# power-switching-TPS6211x.net
KiCad netlist of a schematic drawn in EAGLE
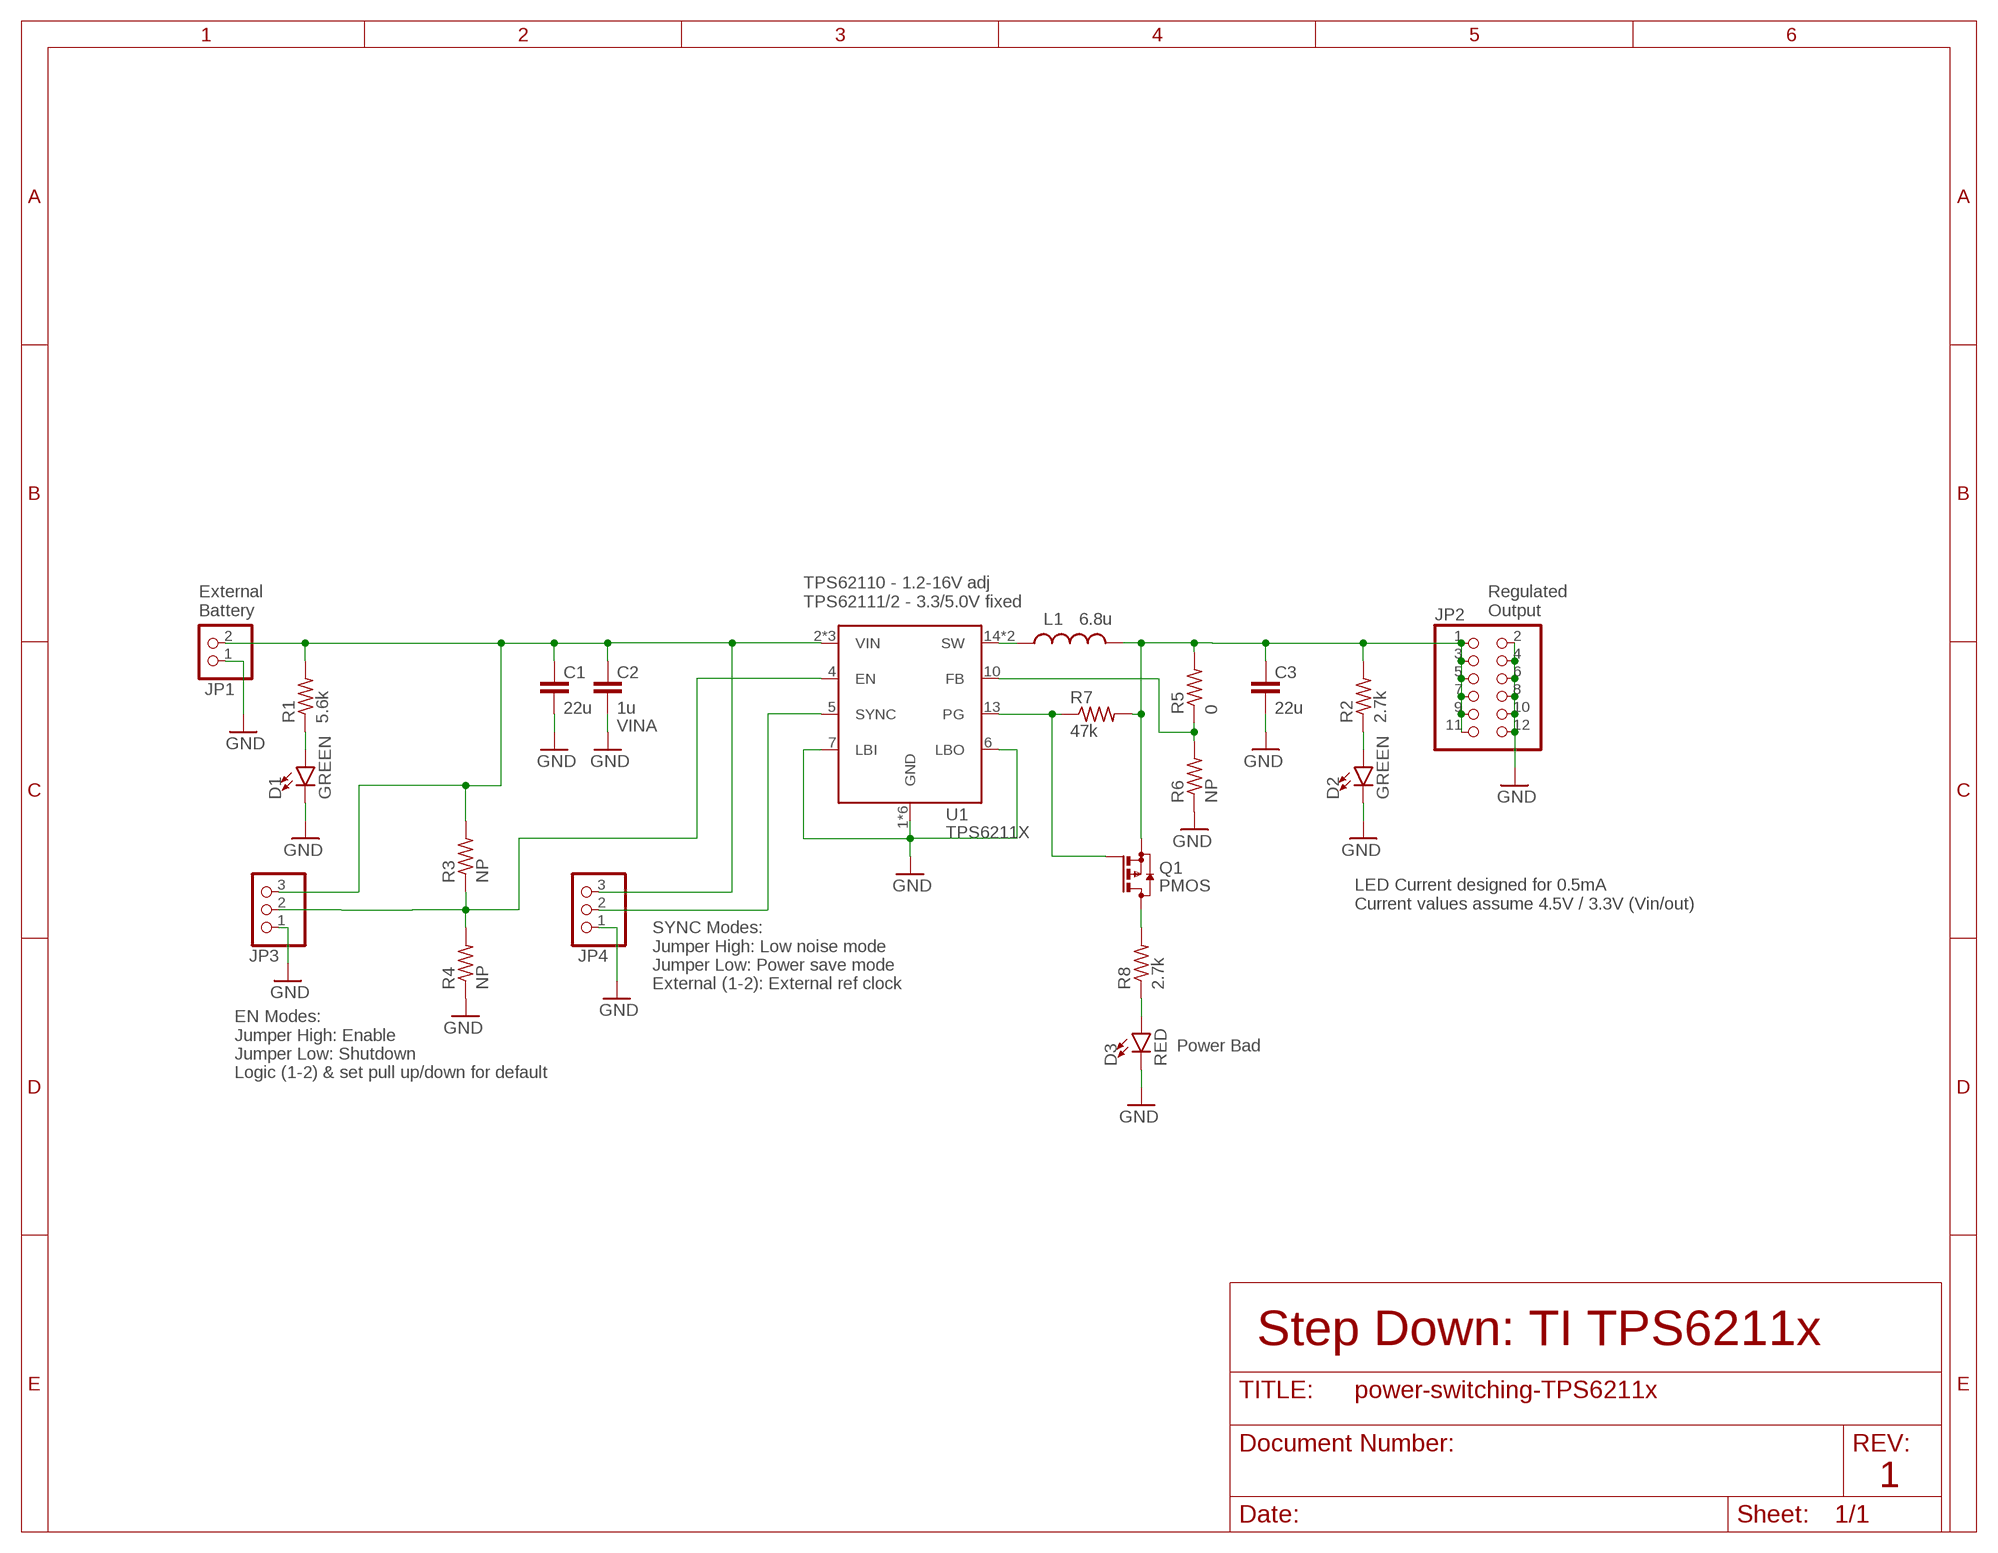
[diagram p0: schematic, sheet 1]

(export (version "E")
  (design (tool "Eeschema 10.0.6"))
  (components
    (comp (ref "C1")
      (value "22u")
      (footprint "eagle-import:1206-B")
      (libsource (lib "eagle-import") (part "C-EU1206-B"))
    )
    (comp (ref "C2")
      (value "1u")
      (footprint "eagle-import:.0603-B-NOSILK")
      (libsource (lib "eagle-import") (part "C-EU0603-B-NOSILK"))
    )
    (comp (ref "C3")
      (value "22u")
      (footprint "eagle-import:1206-B")
      (libsource (lib "eagle-import") (part "C-EU1206-B"))
    )
    (comp (ref "D1")
      (value "GREEN")
      (footprint "eagle-import:LED-0603")
      (libsource (lib "eagle-import") (part "LED-GREEN0603"))
    )
    (comp (ref "D2")
      (value "GREEN")
      (footprint "eagle-import:LED-0603")
      (libsource (lib "eagle-import") (part "LED-GREEN0603"))
    )
    (comp (ref "D3")
      (value "RED")
      (footprint "eagle-import:LED-0603")
      (libsource (lib "eagle-import") (part "LED-GREEN0603"))
    )
    (comp (ref "JP1")
      (value "PINHD-1X2")
      (footprint "eagle-import:1X02")
      (libsource (lib "eagle-import") (part "PINHD-1X2"))
    )
    (comp (ref "JP2")
      (value "PINHD-2X6")
      (footprint "eagle-import:2X06")
      (libsource (lib "eagle-import") (part "PINHD-2X6"))
    )
    (comp (ref "JP3")
      (value "PINHD-1X3")
      (footprint "eagle-import:1X03")
      (libsource (lib "eagle-import") (part "PINHD-1X3"))
    )
    (comp (ref "JP4")
      (value "PINHD-1X3")
      (footprint "eagle-import:1X03")
      (libsource (lib "eagle-import") (part "PINHD-1X3"))
    )
    (comp (ref "L1")
      (value "6.8u")
      (footprint "eagle-import:ECS-MPI4040")
      (fields (field (name "MFR") "ECS") (field (name "MPN") "ECS-MPI4040R4-6R8-R"))
      (libsource (lib "eagle-import") (part "L-ECS-MPI4040"))
    )
    (comp (ref "Q1")
      (value "PMOS")
      (footprint "eagle-import:SOT23")
      (libsource (lib "eagle-import") (part "BSS84"))
    )
    (comp (ref "R1")
      (value "5.6k")
      (footprint "eagle-import:.0603-B-NOSILK")
      (libsource (lib "eagle-import") (part "R-US_0603-B-NOSILK"))
    )
    (comp (ref "R2")
      (value "2.7k")
      (footprint "eagle-import:.0603-B-NOSILK")
      (libsource (lib "eagle-import") (part "R-US_0603-B-NOSILK"))
    )
    (comp (ref "R3")
      (value "NP")
      (footprint "eagle-import:.0402-B-NOSILK")
      (libsource (lib "eagle-import") (part "R-US_0402-B-NOSILK"))
    )
    (comp (ref "R4")
      (value "NP")
      (footprint "eagle-import:.0402-B-NOSILK")
      (libsource (lib "eagle-import") (part "R-US_0402-B-NOSILK"))
    )
    (comp (ref "R5")
      (value "0")
      (footprint "eagle-import:.0402-B-NOSILK")
      (libsource (lib "eagle-import") (part "R-US_0402-B-NOSILK"))
    )
    (comp (ref "R6")
      (value "NP")
      (footprint "eagle-import:.0402-B-NOSILK")
      (libsource (lib "eagle-import") (part "R-US_0402-B-NOSILK"))
    )
    (comp (ref "R7")
      (value "47k")
      (footprint "eagle-import:.0402-B-NOSILK")
      (libsource (lib "eagle-import") (part "R-US_0402-B-NOSILK"))
    )
    (comp (ref "R8")
      (value "2.7k")
      (footprint "eagle-import:.0603-B-NOSILK")
      (libsource (lib "eagle-import") (part "R-US_0603-B-NOSILK"))
    )
    (comp (ref "U1")
      (value "TPS6211X")
      (footprint "eagle-import:S-PVQFN-16")
      (libsource (lib "eagle-import") (part "TPS6211X"))
    )
  )
  (nets
    (net (code "1") (name "GND") (class "Default")
      (node (ref "C1") (pin "2") (pinfunction "2_2") (pintype "passive"))
      (node (ref "C2") (pin "2") (pinfunction "2_2") (pintype "passive"))
      (node (ref "C3") (pin "2") (pinfunction "2_2") (pintype "passive"))
      (node (ref "D1") (pin "C") (pinfunction "C_C") (pintype "passive"))
      (node (ref "D2") (pin "C") (pinfunction "C_C") (pintype "passive"))
      (node (ref "D3") (pin "C") (pinfunction "C_C") (pintype "passive"))
      (node (ref "JP1") (pin "1") (pinfunction "1_1") (pintype "passive"))
      (node (ref "JP2") (pin "10") (pinfunction "10_10") (pintype "passive"))
      (node (ref "JP2") (pin "12") (pinfunction "12_12") (pintype "passive"))
      (node (ref "JP2") (pin "2") (pinfunction "2_2") (pintype "passive"))
      (node (ref "JP2") (pin "4") (pinfunction "4_4") (pintype "passive"))
      (node (ref "JP2") (pin "6") (pinfunction "6_6") (pintype "passive"))
      (node (ref "JP2") (pin "8") (pinfunction "8_8") (pintype "passive"))
      (node (ref "JP3") (pin "1") (pinfunction "1_1") (pintype "passive"))
      (node (ref "JP4") (pin "1") (pinfunction "1_1") (pintype "passive"))
      (node (ref "R4") (pin "1") (pinfunction "1_1") (pintype "passive"))
      (node (ref "R6") (pin "1") (pinfunction "1_1") (pintype "passive"))
      (node (ref "U1") (pin "1") (pinfunction "GND_1") (pintype "power_in"))
      (node (ref "U1") (pin "11") (pinfunction "GND_11") (pintype "power_in"))
      (node (ref "U1") (pin "12") (pinfunction "GND_12") (pintype "power_in"))
      (node (ref "U1") (pin "16") (pinfunction "GND_16") (pintype "power_in"))
      (node (ref "U1") (pin "6") (pinfunction "LBO_6") (pintype "open_collector"))
      (node (ref "U1") (pin "7") (pinfunction "LBI_7") (pintype "input"))
      (node (ref "U1") (pin "9") (pinfunction "GND_9") (pintype "power_in"))
      (node (ref "U1") (pin "PAD") (pinfunction "GND_PAD") (pintype "power_in"))
    )
    (net (code "2") (name "Net-(C1-Pad1)") (class "Default")
      (node (ref "C1") (pin "1") (pinfunction "1_1") (pintype "passive"))
      (node (ref "C2") (pin "1") (pinfunction "1_1") (pintype "passive"))
      (node (ref "JP1") (pin "2") (pinfunction "2_2") (pintype "passive"))
      (node (ref "JP3") (pin "3") (pinfunction "3_3") (pintype "passive"))
      (node (ref "JP4") (pin "3") (pinfunction "3_3") (pintype "passive"))
      (node (ref "R1") (pin "2") (pinfunction "2_2") (pintype "passive"))
      (node (ref "R3") (pin "2") (pinfunction "2_2") (pintype "passive"))
      (node (ref "U1") (pin "2") (pinfunction "VIN_2") (pintype "power_in"))
      (node (ref "U1") (pin "3") (pinfunction "VIN_3") (pintype "power_in"))
      (node (ref "U1") (pin "8") (pinfunction "VIN_8") (pintype "power_in"))
    )
    (net (code "3") (name "Net-(D1-PadA)") (class "Default")
      (node (ref "D1") (pin "A") (pinfunction "A_A") (pintype "passive"))
      (node (ref "R1") (pin "1") (pinfunction "1_1") (pintype "passive"))
    )
    (net (code "4") (name "Net-(D2-PadA)") (class "Default")
      (node (ref "D2") (pin "A") (pinfunction "A_A") (pintype "passive"))
      (node (ref "R2") (pin "1") (pinfunction "1_1") (pintype "passive"))
    )
    (net (code "5") (name "Net-(D3-PadA)") (class "Default")
      (node (ref "D3") (pin "A") (pinfunction "A_A") (pintype "passive"))
      (node (ref "R8") (pin "1") (pinfunction "1_1") (pintype "passive"))
    )
    (net (code "6") (name "Net-(L1-Pad1)") (class "Default")
      (node (ref "L1") (pin "1") (pinfunction "1_1") (pintype "passive"))
      (node (ref "U1") (pin "14") (pinfunction "SW_14") (pintype "output"))
      (node (ref "U1") (pin "15") (pinfunction "SW_15") (pintype "output"))
    )
    (net (code "7") (name "Net-(Q1-D)") (class "Default")
      (node (ref "Q1") (pin "3") (pinfunction "D_3") (pintype "passive"))
      (node (ref "R8") (pin "2") (pinfunction "2_2") (pintype "passive"))
    )
    (net (code "8") (name "Net-(Q1-G)") (class "Default")
      (node (ref "Q1") (pin "1") (pinfunction "G_1") (pintype "passive"))
      (node (ref "R7") (pin "1") (pinfunction "1_1") (pintype "passive"))
      (node (ref "U1") (pin "13") (pinfunction "PG_13") (pintype "open_collector"))
    )
    (net (code "9") (name "Net-(Q1-S)") (class "Default")
      (node (ref "C3") (pin "1") (pinfunction "1_1") (pintype "passive"))
      (node (ref "JP2") (pin "1") (pinfunction "1_1") (pintype "passive"))
      (node (ref "JP2") (pin "11") (pinfunction "11_11") (pintype "passive"))
      (node (ref "JP2") (pin "3") (pinfunction "3_3") (pintype "passive"))
      (node (ref "JP2") (pin "5") (pinfunction "5_5") (pintype "passive"))
      (node (ref "JP2") (pin "7") (pinfunction "7_7") (pintype "passive"))
      (node (ref "JP2") (pin "9") (pinfunction "9_9") (pintype "passive"))
      (node (ref "L1") (pin "2") (pinfunction "2_2") (pintype "passive"))
      (node (ref "Q1") (pin "2") (pinfunction "S_2") (pintype "passive"))
      (node (ref "R2") (pin "2") (pinfunction "2_2") (pintype "passive"))
      (node (ref "R5") (pin "2") (pinfunction "2_2") (pintype "passive"))
      (node (ref "R7") (pin "2") (pinfunction "2_2") (pintype "passive"))
    )
    (net (code "10") (name "Net-(U1-EN)") (class "Default")
      (node (ref "JP3") (pin "2") (pinfunction "2_2") (pintype "passive"))
      (node (ref "R3") (pin "1") (pinfunction "1_1") (pintype "passive"))
      (node (ref "R4") (pin "2") (pinfunction "2_2") (pintype "passive"))
      (node (ref "U1") (pin "4") (pinfunction "EN_4") (pintype "input"))
    )
    (net (code "11") (name "Net-(U1-FB)") (class "Default")
      (node (ref "R5") (pin "1") (pinfunction "1_1") (pintype "passive"))
      (node (ref "R6") (pin "2") (pinfunction "2_2") (pintype "passive"))
      (node (ref "U1") (pin "10") (pinfunction "FB_10") (pintype "input"))
    )
    (net (code "12") (name "Net-(U1-SYNC)") (class "Default")
      (node (ref "JP4") (pin "2") (pinfunction "2_2") (pintype "passive"))
      (node (ref "U1") (pin "5") (pinfunction "SYNC_5") (pintype "input"))
    )
  )
)
